# sensors.net
KiCad netlist of a schematic drawn in EAGLE
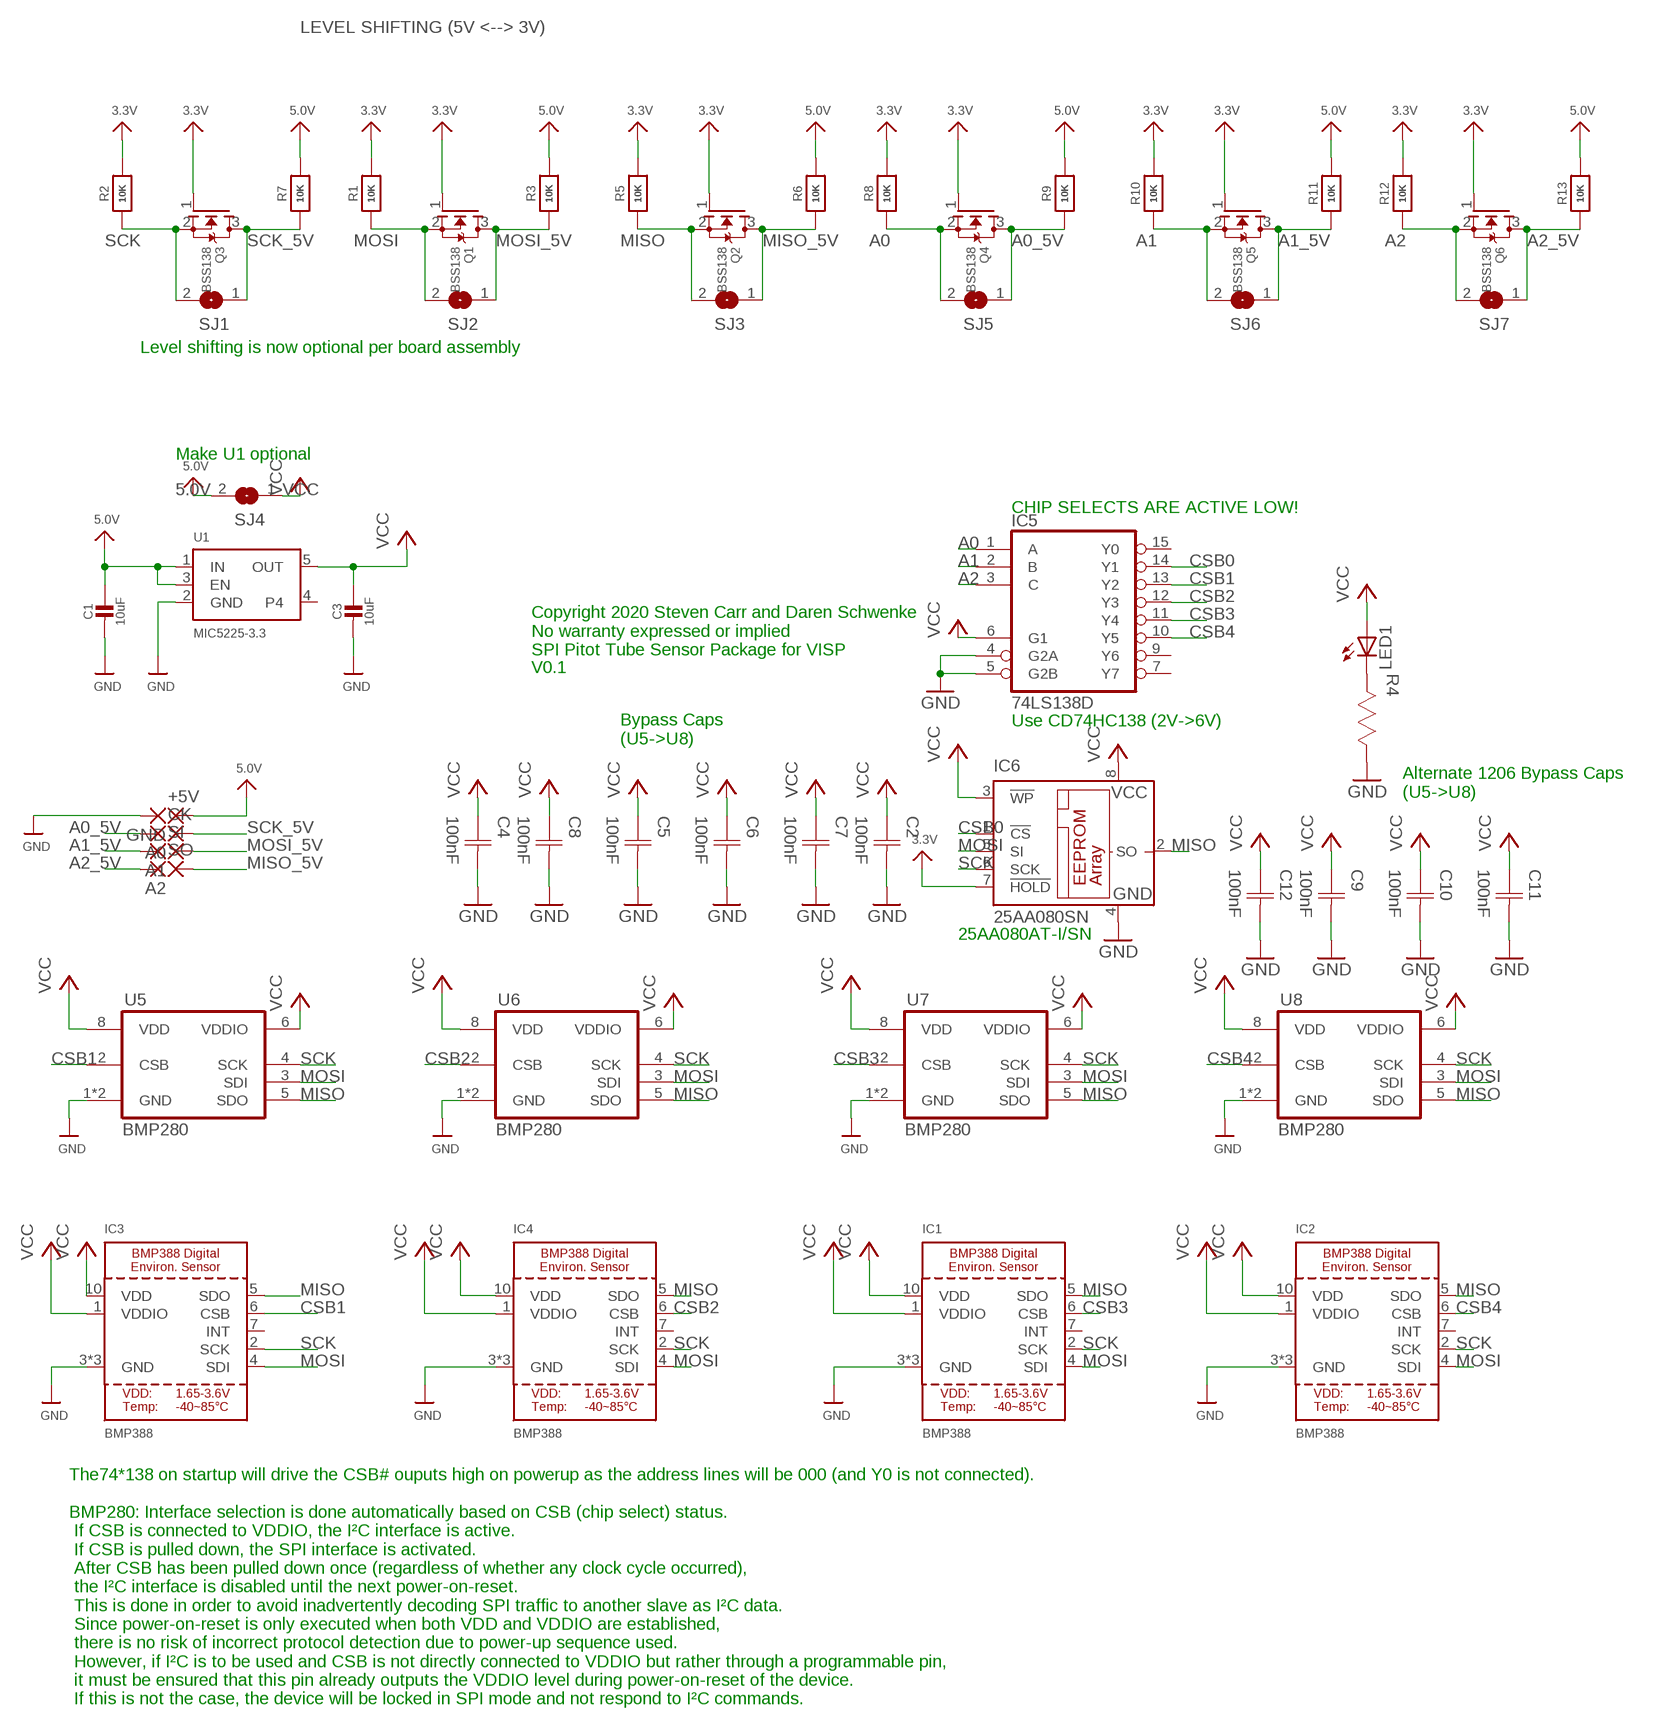
[diagram p0: schematic, sheet 1]

(export (version "E")
  (design (tool "Eeschema 10.0.6"))
  (components
    (comp (ref "+5V")
      (value "SMD2")
      (footprint "eagle-import:SMD1,27-2,54")
      (libsource (lib "eagle-import") (part "SMD2"))
    )
    (comp (ref "A0")
      (value "SMD2")
      (footprint "eagle-import:SMD1,27-2,54")
      (libsource (lib "eagle-import") (part "SMD2"))
    )
    (comp (ref "A1")
      (value "SMD2")
      (footprint "eagle-import:SMD1,27-2,54")
      (libsource (lib "eagle-import") (part "SMD2"))
    )
    (comp (ref "A2")
      (value "SMD2")
      (footprint "eagle-import:SMD1,27-2,54")
      (libsource (lib "eagle-import") (part "SMD2"))
    )
    (comp (ref "C1")
      (value "10uF")
      (footprint "eagle-import:0603-NO")
      (libsource (lib "eagle-import") (part "CAP_CERAMIC0603_NO"))
    )
    (comp (ref "C2")
      (value "100nF")
      (footprint "eagle-import:CAP0402")
      (libsource (lib "eagle-import") (part "CAPACITOR-0402"))
    )
    (comp (ref "C3")
      (value "10uF")
      (footprint "eagle-import:0603-NO")
      (libsource (lib "eagle-import") (part "CAP_CERAMIC0603_NO"))
    )
    (comp (ref "C4")
      (value "100nF")
      (footprint "eagle-import:CAP0402")
      (libsource (lib "eagle-import") (part "CAPACITOR-0402"))
    )
    (comp (ref "C5")
      (value "100nF")
      (footprint "eagle-import:CAP0402")
      (libsource (lib "eagle-import") (part "CAPACITOR-0402"))
    )
    (comp (ref "C6")
      (value "100nF")
      (footprint "eagle-import:CAP0402")
      (libsource (lib "eagle-import") (part "CAPACITOR-0402"))
    )
    (comp (ref "C7")
      (value "100nF")
      (footprint "eagle-import:CAP0402")
      (libsource (lib "eagle-import") (part "CAPACITOR-0402"))
    )
    (comp (ref "C8")
      (value "100nF")
      (footprint "eagle-import:CAP0402")
      (libsource (lib "eagle-import") (part "CAPACITOR-0402"))
    )
    (comp (ref "C9")
      (value "100nF")
      (footprint "eagle-import:CAP1206")
      (libsource (lib "eagle-import") (part "CAPACITOR-1206"))
    )
    (comp (ref "C10")
      (value "100nF")
      (footprint "eagle-import:CAP1206")
      (libsource (lib "eagle-import") (part "CAPACITOR-1206"))
    )
    (comp (ref "C11")
      (value "100nF")
      (footprint "eagle-import:CAP1206")
      (libsource (lib "eagle-import") (part "CAPACITOR-1206"))
    )
    (comp (ref "C12")
      (value "100nF")
      (footprint "eagle-import:CAP1206")
      (libsource (lib "eagle-import") (part "CAPACITOR-1206"))
    )
    (comp (ref "CK")
      (value "SMD2")
      (footprint "eagle-import:SMD1,27-2,54")
      (libsource (lib "eagle-import") (part "SMD2"))
    )
    (comp (ref "GND")
      (value "SMD2")
      (footprint "eagle-import:SMD1,27-2,54")
      (libsource (lib "eagle-import") (part "SMD2"))
    )
    (comp (ref "IC1")
      (value "BMP388")
      (footprint "eagle-import:BMP388")
      (libsource (lib "eagle-import") (part "BMP388"))
    )
    (comp (ref "IC2")
      (value "BMP388")
      (footprint "eagle-import:BMP388")
      (libsource (lib "eagle-import") (part "BMP388"))
    )
    (comp (ref "IC3")
      (value "BMP388")
      (footprint "eagle-import:BMP388")
      (libsource (lib "eagle-import") (part "BMP388"))
    )
    (comp (ref "IC4")
      (value "BMP388")
      (footprint "eagle-import:BMP388")
      (libsource (lib "eagle-import") (part "BMP388"))
    )
    (comp (ref "IC5")
      (value "74LS138D")
      (footprint "eagle-import:SO16")
      (fields (field (name "MPN") "CD74LS138D"))
      (libsource (lib "eagle-import") (part "74138DLS"))
    )
    (comp (ref "IC6")
      (value "25AA080SN")
      (footprint "eagle-import:SO-08")
      (libsource (lib "eagle-import") (part "25SNAA080"))
    )
    (comp (ref "LED1")
      (value "LEDCHIP-LED0603")
      (footprint "eagle-import:CHIP-LED0603")
      (libsource (lib "eagle-import") (part "LEDCHIP-LED0603"))
    )
    (comp (ref "Q1")
      (value "BSS138")
      (footprint "eagle-import:SOT23-WIDE")
      (libsource (lib "eagle-import") (part "MOSFET-NWIDE"))
    )
    (comp (ref "Q2")
      (value "BSS138")
      (footprint "eagle-import:SOT23-WIDE")
      (libsource (lib "eagle-import") (part "MOSFET-NWIDE"))
    )
    (comp (ref "Q3")
      (value "BSS138")
      (footprint "eagle-import:SOT23-WIDE")
      (libsource (lib "eagle-import") (part "MOSFET-NWIDE"))
    )
    (comp (ref "Q4")
      (value "BSS138")
      (footprint "eagle-import:SOT23-WIDE")
      (libsource (lib "eagle-import") (part "MOSFET-NWIDE"))
    )
    (comp (ref "Q5")
      (value "BSS138")
      (footprint "eagle-import:SOT23-WIDE")
      (libsource (lib "eagle-import") (part "MOSFET-NWIDE"))
    )
    (comp (ref "Q6")
      (value "BSS138")
      (footprint "eagle-import:SOT23-WIDE")
      (libsource (lib "eagle-import") (part "MOSFET-NWIDE"))
    )
    (comp (ref "R1")
      (value "10K")
      (footprint "eagle-import:0805-NO")
      (libsource (lib "eagle-import") (part "RESISTOR0805_NOOUTLINE"))
    )
    (comp (ref "R2")
      (value "10K")
      (footprint "eagle-import:0805-NO")
      (libsource (lib "eagle-import") (part "RESISTOR0805_NOOUTLINE"))
    )
    (comp (ref "R3")
      (value "10K")
      (footprint "eagle-import:0805-NO")
      (libsource (lib "eagle-import") (part "RESISTOR0805_NOOUTLINE"))
    )
    (comp (ref "R4")
      (value "RESISTOR-0603")
      (footprint "eagle-import:RES0603")
      (libsource (lib "eagle-import") (part "RESISTOR-0603"))
    )
    (comp (ref "R5")
      (value "10K")
      (footprint "eagle-import:0805-NO")
      (libsource (lib "eagle-import") (part "RESISTOR0805_NOOUTLINE"))
    )
    (comp (ref "R6")
      (value "10K")
      (footprint "eagle-import:0805-NO")
      (libsource (lib "eagle-import") (part "RESISTOR0805_NOOUTLINE"))
    )
    (comp (ref "R7")
      (value "10K")
      (footprint "eagle-import:0805-NO")
      (libsource (lib "eagle-import") (part "RESISTOR0805_NOOUTLINE"))
    )
    (comp (ref "R8")
      (value "10K")
      (footprint "eagle-import:0805-NO")
      (libsource (lib "eagle-import") (part "RESISTOR0805_NOOUTLINE"))
    )
    (comp (ref "R9")
      (value "10K")
      (footprint "eagle-import:0805-NO")
      (libsource (lib "eagle-import") (part "RESISTOR0805_NOOUTLINE"))
    )
    (comp (ref "R10")
      (value "10K")
      (footprint "eagle-import:0805-NO")
      (libsource (lib "eagle-import") (part "RESISTOR0805_NOOUTLINE"))
    )
    (comp (ref "R11")
      (value "10K")
      (footprint "eagle-import:0805-NO")
      (libsource (lib "eagle-import") (part "RESISTOR0805_NOOUTLINE"))
    )
    (comp (ref "R12")
      (value "10K")
      (footprint "eagle-import:0805-NO")
      (libsource (lib "eagle-import") (part "RESISTOR0805_NOOUTLINE"))
    )
    (comp (ref "R13")
      (value "10K")
      (footprint "eagle-import:0805-NO")
      (libsource (lib "eagle-import") (part "RESISTOR0805_NOOUTLINE"))
    )
    (comp (ref "SI")
      (value "SMD2")
      (footprint "eagle-import:SMD1,27-2,54")
      (libsource (lib "eagle-import") (part "SMD2"))
    )
    (comp (ref "SJ1") (value "SJ") (footprint "eagle-import:SJ") (libsource (lib "eagle-import") (part "SJ")))
    (comp (ref "SJ2") (value "SJ") (footprint "eagle-import:SJ") (libsource (lib "eagle-import") (part "SJ")))
    (comp (ref "SJ3") (value "SJ") (footprint "eagle-import:SJ") (libsource (lib "eagle-import") (part "SJ")))
    (comp (ref "SJ4") (value "SJ") (footprint "eagle-import:SJ") (libsource (lib "eagle-import") (part "SJ")))
    (comp (ref "SJ5") (value "SJ") (footprint "eagle-import:SJ") (libsource (lib "eagle-import") (part "SJ")))
    (comp (ref "SJ6") (value "SJ") (footprint "eagle-import:SJ") (libsource (lib "eagle-import") (part "SJ")))
    (comp (ref "SJ7") (value "SJ") (footprint "eagle-import:SJ") (libsource (lib "eagle-import") (part "SJ")))
    (comp (ref "SO")
      (value "SMD2")
      (footprint "eagle-import:SMD1,27-2,54")
      (libsource (lib "eagle-import") (part "SMD2"))
    )
    (comp (ref "U1")
      (value "MIC5225-3.3")
      (footprint "eagle-import:SOT23-5")
      (libsource (lib "eagle-import") (part "VREG_SOT23-5"))
    )
    (comp (ref "U5")
      (value "BMP280")
      (footprint "eagle-import:BMP280")
      (libsource (lib "eagle-import") (part "BMP280"))
    )
    (comp (ref "U6")
      (value "BMP280")
      (footprint "eagle-import:BMP280")
      (libsource (lib "eagle-import") (part "BMP280"))
    )
    (comp (ref "U7")
      (value "BMP280")
      (footprint "eagle-import:BMP280")
      (libsource (lib "eagle-import") (part "BMP280"))
    )
    (comp (ref "U8")
      (value "BMP280")
      (footprint "eagle-import:BMP280")
      (libsource (lib "eagle-import") (part "BMP280"))
    )
  )
  (nets
    (net (code "1") (name "/A0") (class "Default")
      (node (ref "IC5") (pin "1") (pinfunction "A_1") (pintype "input"))
      (node (ref "Q4") (pin "2") (pinfunction "S_2") (pintype "bidirectional"))
      (node (ref "R8") (pin "1") (pinfunction "1_1") (pintype "passive"))
      (node (ref "SJ5") (pin "2") (pinfunction "2_2") (pintype "passive"))
    )
    (net (code "2") (name "/A0_5V") (class "Default")
      (node (ref "A0") (pin "1") (pinfunction "P_1") (pintype "passive"))
      (node (ref "Q4") (pin "3") (pinfunction "D_3") (pintype "bidirectional"))
      (node (ref "R9") (pin "1") (pinfunction "1_1") (pintype "passive"))
      (node (ref "SJ5") (pin "1") (pinfunction "1_1") (pintype "passive"))
    )
    (net (code "3") (name "/A1") (class "Default")
      (node (ref "IC5") (pin "2") (pinfunction "B_2") (pintype "input"))
      (node (ref "Q5") (pin "2") (pinfunction "S_2") (pintype "bidirectional"))
      (node (ref "R10") (pin "1") (pinfunction "1_1") (pintype "passive"))
      (node (ref "SJ6") (pin "2") (pinfunction "2_2") (pintype "passive"))
    )
    (net (code "4") (name "/A1_5V") (class "Default")
      (node (ref "A1") (pin "1") (pinfunction "P_1") (pintype "passive"))
      (node (ref "Q5") (pin "3") (pinfunction "D_3") (pintype "bidirectional"))
      (node (ref "R11") (pin "1") (pinfunction "1_1") (pintype "passive"))
      (node (ref "SJ6") (pin "1") (pinfunction "1_1") (pintype "passive"))
    )
    (net (code "5") (name "/A2") (class "Default")
      (node (ref "IC5") (pin "3") (pinfunction "C_3") (pintype "input"))
      (node (ref "Q6") (pin "2") (pinfunction "S_2") (pintype "bidirectional"))
      (node (ref "R12") (pin "1") (pinfunction "1_1") (pintype "passive"))
      (node (ref "SJ7") (pin "2") (pinfunction "2_2") (pintype "passive"))
    )
    (net (code "6") (name "/A2_5V") (class "Default")
      (node (ref "A2") (pin "1") (pinfunction "P_1") (pintype "passive"))
      (node (ref "Q6") (pin "3") (pinfunction "D_3") (pintype "bidirectional"))
      (node (ref "R13") (pin "1") (pinfunction "1_1") (pintype "passive"))
      (node (ref "SJ7") (pin "1") (pinfunction "1_1") (pintype "passive"))
    )
    (net (code "7") (name "/CSB0") (class "Default")
      (node (ref "IC5") (pin "14") (pinfunction "Y1_14") (pintype "output"))
      (node (ref "IC6") (pin "1") (pinfunction "~{CS}_1") (pintype "input"))
    )
    (net (code "8") (name "/CSB1") (class "Default")
      (node (ref "IC3") (pin "6") (pinfunction "CSB_6") (pintype "input"))
      (node (ref "IC5") (pin "13") (pinfunction "Y2_13") (pintype "output"))
      (node (ref "U5") (pin "2") (pinfunction "CSB_2") (pintype "input"))
    )
    (net (code "9") (name "/CSB2") (class "Default")
      (node (ref "IC4") (pin "6") (pinfunction "CSB_6") (pintype "input"))
      (node (ref "IC5") (pin "12") (pinfunction "Y3_12") (pintype "output"))
      (node (ref "U6") (pin "2") (pinfunction "CSB_2") (pintype "input"))
    )
    (net (code "10") (name "/CSB3") (class "Default")
      (node (ref "IC1") (pin "6") (pinfunction "CSB_6") (pintype "input"))
      (node (ref "IC5") (pin "11") (pinfunction "Y4_11") (pintype "output"))
      (node (ref "U7") (pin "2") (pinfunction "CSB_2") (pintype "input"))
    )
    (net (code "11") (name "/CSB4") (class "Default")
      (node (ref "IC2") (pin "6") (pinfunction "CSB_6") (pintype "input"))
      (node (ref "IC5") (pin "10") (pinfunction "Y5_10") (pintype "output"))
      (node (ref "U8") (pin "2") (pinfunction "CSB_2") (pintype "input"))
    )
    (net (code "12") (name "/MISO") (class "Default")
      (node (ref "IC1") (pin "5") (pinfunction "SDO_5") (pintype "output"))
      (node (ref "IC2") (pin "5") (pinfunction "SDO_5") (pintype "output"))
      (node (ref "IC3") (pin "5") (pinfunction "SDO_5") (pintype "output"))
      (node (ref "IC4") (pin "5") (pinfunction "SDO_5") (pintype "output"))
      (node (ref "IC6") (pin "2") (pinfunction "SO_2") (pintype "bidirectional"))
      (node (ref "Q2") (pin "2") (pinfunction "S_2") (pintype "bidirectional"))
      (node (ref "R5") (pin "1") (pinfunction "1_1") (pintype "passive"))
      (node (ref "SJ3") (pin "2") (pinfunction "2_2") (pintype "passive"))
      (node (ref "U5") (pin "5") (pinfunction "SDO_5") (pintype "input"))
      (node (ref "U6") (pin "5") (pinfunction "SDO_5") (pintype "input"))
      (node (ref "U7") (pin "5") (pinfunction "SDO_5") (pintype "input"))
      (node (ref "U8") (pin "5") (pinfunction "SDO_5") (pintype "input"))
    )
    (net (code "13") (name "/MISO_5V") (class "Default")
      (node (ref "Q2") (pin "3") (pinfunction "D_3") (pintype "bidirectional"))
      (node (ref "R6") (pin "1") (pinfunction "1_1") (pintype "passive"))
      (node (ref "SJ3") (pin "1") (pinfunction "1_1") (pintype "passive"))
      (node (ref "SO") (pin "1") (pinfunction "P_1") (pintype "passive"))
    )
    (net (code "14") (name "/MOSI") (class "Default")
      (node (ref "IC1") (pin "4") (pinfunction "SDI_4") (pintype "input"))
      (node (ref "IC2") (pin "4") (pinfunction "SDI_4") (pintype "input"))
      (node (ref "IC3") (pin "4") (pinfunction "SDI_4") (pintype "input"))
      (node (ref "IC4") (pin "4") (pinfunction "SDI_4") (pintype "input"))
      (node (ref "IC6") (pin "5") (pinfunction "SI_5") (pintype "input"))
      (node (ref "Q1") (pin "2") (pinfunction "S_2") (pintype "bidirectional"))
      (node (ref "R1") (pin "1") (pinfunction "1_1") (pintype "passive"))
      (node (ref "SJ2") (pin "2") (pinfunction "2_2") (pintype "passive"))
      (node (ref "U5") (pin "3") (pinfunction "SDI_3") (pintype "bidirectional"))
      (node (ref "U6") (pin "3") (pinfunction "SDI_3") (pintype "bidirectional"))
      (node (ref "U7") (pin "3") (pinfunction "SDI_3") (pintype "bidirectional"))
      (node (ref "U8") (pin "3") (pinfunction "SDI_3") (pintype "bidirectional"))
    )
    (net (code "15") (name "/MOSI_5V") (class "Default")
      (node (ref "Q1") (pin "3") (pinfunction "D_3") (pintype "bidirectional"))
      (node (ref "R3") (pin "1") (pinfunction "1_1") (pintype "passive"))
      (node (ref "SI") (pin "1") (pinfunction "P_1") (pintype "passive"))
      (node (ref "SJ2") (pin "1") (pinfunction "1_1") (pintype "passive"))
    )
    (net (code "16") (name "/SCK") (class "Default")
      (node (ref "IC1") (pin "2") (pinfunction "SCK_2") (pintype "input"))
      (node (ref "IC2") (pin "2") (pinfunction "SCK_2") (pintype "input"))
      (node (ref "IC3") (pin "2") (pinfunction "SCK_2") (pintype "input"))
      (node (ref "IC4") (pin "2") (pinfunction "SCK_2") (pintype "input"))
      (node (ref "IC6") (pin "6") (pinfunction "SCK_6") (pintype "input"))
      (node (ref "Q3") (pin "2") (pinfunction "S_2") (pintype "bidirectional"))
      (node (ref "R2") (pin "1") (pinfunction "1_1") (pintype "passive"))
      (node (ref "SJ1") (pin "2") (pinfunction "2_2") (pintype "passive"))
      (node (ref "U5") (pin "4") (pinfunction "SCK_4") (pintype "bidirectional"))
      (node (ref "U6") (pin "4") (pinfunction "SCK_4") (pintype "bidirectional"))
      (node (ref "U7") (pin "4") (pinfunction "SCK_4") (pintype "bidirectional"))
      (node (ref "U8") (pin "4") (pinfunction "SCK_4") (pintype "bidirectional"))
    )
    (net (code "17") (name "/SCK_5V") (class "Default")
      (node (ref "CK") (pin "1") (pinfunction "P_1") (pintype "passive"))
      (node (ref "Q3") (pin "3") (pinfunction "D_3") (pintype "bidirectional"))
      (node (ref "R7") (pin "1") (pinfunction "1_1") (pintype "passive"))
      (node (ref "SJ1") (pin "1") (pinfunction "1_1") (pintype "passive"))
    )
    (net (code "18") (name "3.3V") (class "Default")
      (node (ref "IC6") (pin "7") (pinfunction "~{HOLD}_7") (pintype "input"))
      (node (ref "Q1") (pin "1") (pinfunction "G_1") (pintype "bidirectional"))
      (node (ref "Q2") (pin "1") (pinfunction "G_1") (pintype "bidirectional"))
      (node (ref "Q3") (pin "1") (pinfunction "G_1") (pintype "bidirectional"))
      (node (ref "Q4") (pin "1") (pinfunction "G_1") (pintype "bidirectional"))
      (node (ref "Q5") (pin "1") (pinfunction "G_1") (pintype "bidirectional"))
      (node (ref "Q6") (pin "1") (pinfunction "G_1") (pintype "bidirectional"))
      (node (ref "R1") (pin "2") (pinfunction "2_2") (pintype "passive"))
      (node (ref "R10") (pin "2") (pinfunction "2_2") (pintype "passive"))
      (node (ref "R12") (pin "2") (pinfunction "2_2") (pintype "passive"))
      (node (ref "R2") (pin "2") (pinfunction "2_2") (pintype "passive"))
      (node (ref "R5") (pin "2") (pinfunction "2_2") (pintype "passive"))
      (node (ref "R8") (pin "2") (pinfunction "2_2") (pintype "passive"))
    )
    (net (code "19") (name "5.0V") (class "Default")
      (node (ref "+5V") (pin "1") (pinfunction "P_1") (pintype "passive"))
      (node (ref "C1") (pin "1") (pinfunction "1_1") (pintype "passive"))
      (node (ref "R11") (pin "2") (pinfunction "2_2") (pintype "passive"))
      (node (ref "R13") (pin "2") (pinfunction "2_2") (pintype "passive"))
      (node (ref "R3") (pin "2") (pinfunction "2_2") (pintype "passive"))
      (node (ref "R6") (pin "2") (pinfunction "2_2") (pintype "passive"))
      (node (ref "R7") (pin "2") (pinfunction "2_2") (pintype "passive"))
      (node (ref "R9") (pin "2") (pinfunction "2_2") (pintype "passive"))
      (node (ref "SJ4") (pin "2") (pinfunction "2_2") (pintype "passive"))
      (node (ref "U1") (pin "1") (pinfunction "IN_1") (pintype "power_in"))
      (node (ref "U1") (pin "3") (pinfunction "EN_3") (pintype "input"))
    )
    (net (code "20") (name "GND") (class "Default")
      (node (ref "C1") (pin "2") (pinfunction "2_2") (pintype "passive"))
      (node (ref "C10") (pin "2") (pinfunction "C2_2") (pintype "passive"))
      (node (ref "C11") (pin "2") (pinfunction "C2_2") (pintype "passive"))
      (node (ref "C12") (pin "2") (pinfunction "C2_2") (pintype "passive"))
      (node (ref "C2") (pin "2") (pinfunction "C2_2") (pintype "passive"))
      (node (ref "C3") (pin "2") (pinfunction "2_2") (pintype "passive"))
      (node (ref "C4") (pin "2") (pinfunction "C2_2") (pintype "passive"))
      (node (ref "C5") (pin "2") (pinfunction "C2_2") (pintype "passive"))
      (node (ref "C6") (pin "2") (pinfunction "C2_2") (pintype "passive"))
      (node (ref "C7") (pin "2") (pinfunction "C2_2") (pintype "passive"))
      (node (ref "C8") (pin "2") (pinfunction "C2_2") (pintype "passive"))
      (node (ref "C9") (pin "2") (pinfunction "C2_2") (pintype "passive"))
      (node (ref "GND") (pin "1") (pinfunction "P_1") (pintype "passive"))
      (node (ref "IC1") (pin "3") (pinfunction "GND_3") (pintype "power_in"))
      (node (ref "IC1") (pin "8") (pinfunction "GND_8") (pintype "power_in"))
      (node (ref "IC1") (pin "9") (pinfunction "GND_9") (pintype "power_in"))
      (node (ref "IC2") (pin "3") (pinfunction "GND_3") (pintype "power_in"))
      (node (ref "IC2") (pin "8") (pinfunction "GND_8") (pintype "power_in"))
      (node (ref "IC2") (pin "9") (pinfunction "GND_9") (pintype "power_in"))
      (node (ref "IC3") (pin "3") (pinfunction "GND_3") (pintype "power_in"))
      (node (ref "IC3") (pin "8") (pinfunction "GND_8") (pintype "power_in"))
      (node (ref "IC3") (pin "9") (pinfunction "GND_9") (pintype "power_in"))
      (node (ref "IC4") (pin "3") (pinfunction "GND_3") (pintype "power_in"))
      (node (ref "IC4") (pin "8") (pinfunction "GND_8") (pintype "power_in"))
      (node (ref "IC4") (pin "9") (pinfunction "GND_9") (pintype "power_in"))
      (node (ref "IC5") (pin "4") (pinfunction "G2A_4") (pintype "input"))
      (node (ref "IC5") (pin "5") (pinfunction "G2B_5") (pintype "input"))
      (node (ref "IC6") (pin "4") (pinfunction "GND_4") (pintype "power_in"))
      (node (ref "R4") (pin "1") (pinfunction "1_1") (pintype "passive"))
      (node (ref "U1") (pin "2") (pinfunction "GND_2") (pintype "power_in"))
      (node (ref "U5") (pin "1") (pinfunction "GND_1") (pintype "power_in"))
      (node (ref "U5") (pin "7") (pinfunction "GND_7") (pintype "power_in"))
      (node (ref "U6") (pin "1") (pinfunction "GND_1") (pintype "power_in"))
      (node (ref "U6") (pin "7") (pinfunction "GND_7") (pintype "power_in"))
      (node (ref "U7") (pin "1") (pinfunction "GND_1") (pintype "power_in"))
      (node (ref "U7") (pin "7") (pinfunction "GND_7") (pintype "power_in"))
      (node (ref "U8") (pin "1") (pinfunction "GND_1") (pintype "power_in"))
      (node (ref "U8") (pin "7") (pinfunction "GND_7") (pintype "power_in"))
    )
    (net (code "21") (name "Net-(LED1-PadC)") (class "Default")
      (node (ref "LED1") (pin "C") (pinfunction "C_C") (pintype "passive"))
      (node (ref "R4") (pin "2") (pinfunction "2_2") (pintype "passive"))
    )
    (net (code "22") (name "VCC") (class "Default")
      (node (ref "C10") (pin "1") (pinfunction "C1_1") (pintype "passive"))
      (node (ref "C11") (pin "1") (pinfunction "C1_1") (pintype "passive"))
      (node (ref "C12") (pin "1") (pinfunction "C1_1") (pintype "passive"))
      (node (ref "C2") (pin "1") (pinfunction "C1_1") (pintype "passive"))
      (node (ref "C3") (pin "1") (pinfunction "1_1") (pintype "passive"))
      (node (ref "C4") (pin "1") (pinfunction "C1_1") (pintype "passive"))
      (node (ref "C5") (pin "1") (pinfunction "C1_1") (pintype "passive"))
      (node (ref "C6") (pin "1") (pinfunction "C1_1") (pintype "passive"))
      (node (ref "C7") (pin "1") (pinfunction "C1_1") (pintype "passive"))
      (node (ref "C8") (pin "1") (pinfunction "C1_1") (pintype "passive"))
      (node (ref "C9") (pin "1") (pinfunction "C1_1") (pintype "passive"))
      (node (ref "IC1") (pin "1") (pinfunction "VDDIO_1") (pintype "power_in"))
      (node (ref "IC1") (pin "10") (pinfunction "VDD_10") (pintype "power_in"))
      (node (ref "IC2") (pin "1") (pinfunction "VDDIO_1") (pintype "power_in"))
      (node (ref "IC2") (pin "10") (pinfunction "VDD_10") (pintype "power_in"))
      (node (ref "IC3") (pin "1") (pinfunction "VDDIO_1") (pintype "power_in"))
      (node (ref "IC3") (pin "10") (pinfunction "VDD_10") (pintype "power_in"))
      (node (ref "IC4") (pin "1") (pinfunction "VDDIO_1") (pintype "power_in"))
      (node (ref "IC4") (pin "10") (pinfunction "VDD_10") (pintype "power_in"))
      (node (ref "IC5") (pin "6") (pinfunction "G1_6") (pintype "input"))
      (node (ref "IC6") (pin "3") (pinfunction "~{WP}_3") (pintype "input"))
      (node (ref "IC6") (pin "8") (pinfunction "VCC_8") (pintype "power_in"))
      (node (ref "LED1") (pin "A") (pinfunction "A_A") (pintype "passive"))
      (node (ref "SJ4") (pin "1") (pinfunction "1_1") (pintype "passive"))
      (node (ref "U1") (pin "5") (pinfunction "OUT_5") (pintype "power_in"))
      (node (ref "U5") (pin "6") (pinfunction "VDDIO_6") (pintype "power_in"))
      (node (ref "U5") (pin "8") (pinfunction "VDD_8") (pintype "power_in"))
      (node (ref "U6") (pin "6") (pinfunction "VDDIO_6") (pintype "power_in"))
      (node (ref "U6") (pin "8") (pinfunction "VDD_8") (pintype "power_in"))
      (node (ref "U7") (pin "6") (pinfunction "VDDIO_6") (pintype "power_in"))
      (node (ref "U7") (pin "8") (pinfunction "VDD_8") (pintype "power_in"))
      (node (ref "U8") (pin "6") (pinfunction "VDDIO_6") (pintype "power_in"))
      (node (ref "U8") (pin "8") (pinfunction "VDD_8") (pintype "power_in"))
    )
    (net (code "23") (name "unconnected-(IC1-INT-Pad7)") (class "Default")
      (node (ref "IC1") (pin "7") (pinfunction "INT_7") (pintype "output"))
    )
    (net (code "24") (name "unconnected-(IC2-INT-Pad7)") (class "Default")
      (node (ref "IC2") (pin "7") (pinfunction "INT_7") (pintype "output"))
    )
    (net (code "25") (name "unconnected-(IC3-INT-Pad7)") (class "Default")
      (node (ref "IC3") (pin "7") (pinfunction "INT_7") (pintype "output"))
    )
    (net (code "26") (name "unconnected-(IC4-INT-Pad7)") (class "Default")
      (node (ref "IC4") (pin "7") (pinfunction "INT_7") (pintype "output"))
    )
    (net (code "27") (name "unconnected-(IC5A-Y0-Pad15)") (class "Default")
      (node (ref "IC5") (pin "15") (pinfunction "Y0_15") (pintype "output"))
    )
    (net (code "28") (name "unconnected-(IC5A-Y6-Pad9)") (class "Default")
      (node (ref "IC5") (pin "9") (pinfunction "Y6_9") (pintype "output"))
    )
    (net (code "29") (name "unconnected-(IC5A-Y7-Pad7)") (class "Default")
      (node (ref "IC5") (pin "7") (pinfunction "Y7_7") (pintype "output"))
    )
    (net (code "30") (name "unconnected-(U1-P4-Pad4)") (class "Default")
      (node (ref "U1") (pin "4") (pinfunction "P4_4") (pintype "bidirectional"))
    )
  )
)
